# es9023.net
KiCad netlist of a schematic drawn in EAGLE
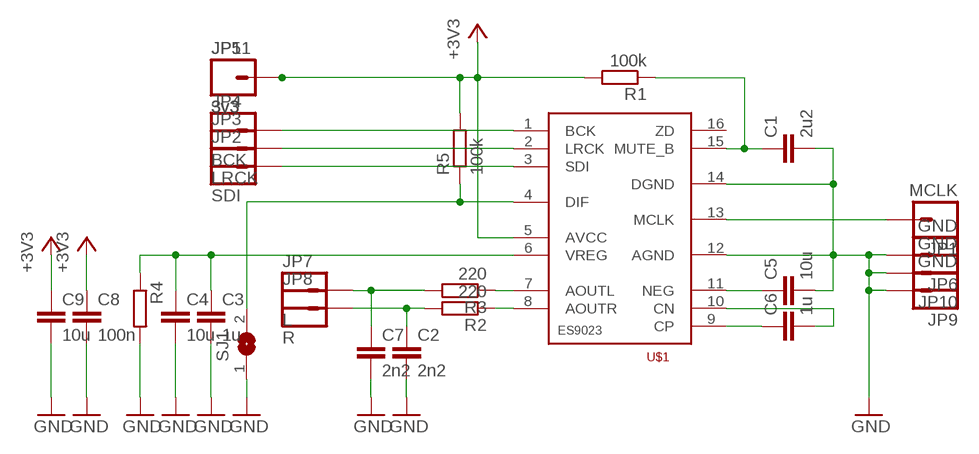
[diagram p0: schematic, sheet 1]

(export (version "E")
  (design (tool "Eeschema 10.0.6"))
  (components
    (comp (ref "C1")
      (value "2u2")
      (footprint "eagle-import:C0805K")
      (libsource (lib "eagle-import") (part "C-EUC0805K"))
    )
    (comp (ref "C2")
      (value "2n2")
      (footprint "eagle-import:C0805K")
      (libsource (lib "eagle-import") (part "C-EUC0805K"))
    )
    (comp (ref "C3")
      (value "1u")
      (footprint "eagle-import:C0805K")
      (libsource (lib "eagle-import") (part "C-EUC0805K"))
    )
    (comp (ref "C4")
      (value "10u")
      (footprint "eagle-import:C0805K")
      (libsource (lib "eagle-import") (part "C-EUC0805K"))
    )
    (comp (ref "C5")
      (value "10u")
      (footprint "eagle-import:C0805K")
      (libsource (lib "eagle-import") (part "C-EUC0805K"))
    )
    (comp (ref "C6")
      (value "1u")
      (footprint "eagle-import:C0805K")
      (libsource (lib "eagle-import") (part "C-EUC0805K"))
    )
    (comp (ref "C7")
      (value "2n2")
      (footprint "eagle-import:C0805K")
      (libsource (lib "eagle-import") (part "C-EUC0805K"))
    )
    (comp (ref "C8")
      (value "100n")
      (footprint "eagle-import:C0805K")
      (libsource (lib "eagle-import") (part "C-EUC0805K"))
    )
    (comp (ref "C9")
      (value "10u")
      (footprint "eagle-import:C0805K")
      (libsource (lib "eagle-import") (part "C-EUC0805K"))
    )
    (comp (ref "JP1")
      (value "MCLK")
      (footprint "eagle-import:1X01_LONGPAD")
      (libsource (lib "eagle-import") (part "M01PTH_LONGPAD"))
    )
    (comp (ref "JP2")
      (value "SDI")
      (footprint "eagle-import:1X01_LONGPAD")
      (libsource (lib "eagle-import") (part "M01PTH_LONGPAD"))
    )
    (comp (ref "JP3")
      (value "LRCK")
      (footprint "eagle-import:1X01_LONGPAD")
      (libsource (lib "eagle-import") (part "M01PTH_LONGPAD"))
    )
    (comp (ref "JP4")
      (value "BCK")
      (footprint "eagle-import:1X01_LONGPAD")
      (libsource (lib "eagle-import") (part "M01PTH_LONGPAD"))
    )
    (comp (ref "JP5")
      (value "3v3")
      (footprint "eagle-import:1X01_LONGPAD")
      (libsource (lib "eagle-import") (part "M01PTH_LONGPAD"))
    )
    (comp (ref "JP6")
      (value "GND")
      (footprint "eagle-import:1X01_LONGPAD")
      (libsource (lib "eagle-import") (part "M01PTH_LONGPAD"))
    )
    (comp (ref "JP7")
      (value "L")
      (footprint "eagle-import:1X01_LONGPAD")
      (libsource (lib "eagle-import") (part "M01PTH_LONGPAD"))
    )
    (comp (ref "JP8")
      (value "R")
      (footprint "eagle-import:1X01_LONGPAD")
      (libsource (lib "eagle-import") (part "M01PTH_LONGPAD"))
    )
    (comp (ref "JP9")
      (value "GND")
      (footprint "eagle-import:1X01_LONGPAD")
      (libsource (lib "eagle-import") (part "M01PTH_LONGPAD"))
    )
    (comp (ref "JP10")
      (value "GND")
      (footprint "eagle-import:1X01_LONGPAD")
      (libsource (lib "eagle-import") (part "M01PTH_LONGPAD"))
    )
    (comp (ref "JP11")
      (value "3v3")
      (footprint "eagle-import:1X01_LONGPAD")
      (libsource (lib "eagle-import") (part "M01PTH_LONGPAD"))
    )
    (comp (ref "R1")
      (value "100k")
      (footprint "eagle-import:M0805")
      (libsource (lib "eagle-import") (part "R-EU_M0805"))
    )
    (comp (ref "R2")
      (value "220")
      (footprint "eagle-import:M0805")
      (libsource (lib "eagle-import") (part "R-EU_M0805"))
    )
    (comp (ref "R3")
      (value "220")
      (footprint "eagle-import:M0805")
      (libsource (lib "eagle-import") (part "R-EU_M0805"))
    )
    (comp (ref "R4")
      (value "R-EU_M0805")
      (footprint "eagle-import:M0805")
      (libsource (lib "eagle-import") (part "R-EU_M0805"))
    )
    (comp (ref "R5")
      (value "100k")
      (footprint "eagle-import:M0805")
      (libsource (lib "eagle-import") (part "R-EU_M0805"))
    )
    (comp (ref "SJ1") (value "SJ") (footprint "eagle-import:SJ") (libsource (lib "eagle-import") (part "SJ")))
    (comp (ref "U$1")
      (value "ES9023-SMD")
      (footprint "eagle-import:SOP16")
      (libsource (lib "eagle-import") (part "ES9023-SMD"))
    )
  )
  (nets
    (net (code "1") (name "+3V3") (class "Default")
      (node (ref "C8") (pin "1") (pinfunction "1_1") (pintype "passive"))
      (node (ref "C9") (pin "1") (pinfunction "1_1") (pintype "passive"))
      (node (ref "JP11") (pin "1") (pinfunction "1_1") (pintype "passive"))
      (node (ref "JP5") (pin "1") (pinfunction "1_1") (pintype "passive"))
      (node (ref "R1") (pin "2") (pinfunction "2_2") (pintype "passive"))
      (node (ref "R5") (pin "2") (pinfunction "2_2") (pintype "passive"))
      (node (ref "U$1") (pin "5") (pinfunction "AVCC_5") (pintype "bidirectional"))
    )
    (net (code "2") (name "GND") (class "Default")
      (node (ref "C1") (pin "2") (pinfunction "2_2") (pintype "passive"))
      (node (ref "C2") (pin "2") (pinfunction "2_2") (pintype "passive"))
      (node (ref "C3") (pin "2") (pinfunction "2_2") (pintype "passive"))
      (node (ref "C4") (pin "2") (pinfunction "2_2") (pintype "passive"))
      (node (ref "C5") (pin "2") (pinfunction "2_2") (pintype "passive"))
      (node (ref "C7") (pin "2") (pinfunction "2_2") (pintype "passive"))
      (node (ref "C8") (pin "2") (pinfunction "2_2") (pintype "passive"))
      (node (ref "C9") (pin "2") (pinfunction "2_2") (pintype "passive"))
      (node (ref "JP10") (pin "1") (pinfunction "1_1") (pintype "passive"))
      (node (ref "JP6") (pin "1") (pinfunction "1_1") (pintype "passive"))
      (node (ref "JP9") (pin "1") (pinfunction "1_1") (pintype "passive"))
      (node (ref "R4") (pin "2") (pinfunction "2_2") (pintype "passive"))
      (node (ref "SJ1") (pin "1") (pinfunction "1_1") (pintype "passive"))
      (node (ref "U$1") (pin "12") (pinfunction "AGND_12") (pintype "bidirectional"))
      (node (ref "U$1") (pin "14") (pinfunction "DGND_14") (pintype "bidirectional"))
    )
    (net (code "3") (name "Net-(C2-Pad1)") (class "Default")
      (node (ref "C2") (pin "1") (pinfunction "1_1") (pintype "passive"))
      (node (ref "JP8") (pin "1") (pinfunction "1_1") (pintype "passive"))
      (node (ref "R2") (pin "2") (pinfunction "2_2") (pintype "passive"))
    )
    (net (code "4") (name "Net-(C7-Pad1)") (class "Default")
      (node (ref "C7") (pin "1") (pinfunction "1_1") (pintype "passive"))
      (node (ref "JP7") (pin "1") (pinfunction "1_1") (pintype "passive"))
      (node (ref "R3") (pin "2") (pinfunction "2_2") (pintype "passive"))
    )
    (net (code "5") (name "Net-(U$1-AOUTL)") (class "Default")
      (node (ref "R3") (pin "1") (pinfunction "1_1") (pintype "passive"))
      (node (ref "U$1") (pin "7") (pinfunction "AOUTL_7") (pintype "bidirectional"))
    )
    (net (code "6") (name "Net-(U$1-AOUTR)") (class "Default")
      (node (ref "R2") (pin "1") (pinfunction "1_1") (pintype "passive"))
      (node (ref "U$1") (pin "8") (pinfunction "AOUTR_8") (pintype "bidirectional"))
    )
    (net (code "7") (name "Net-(U$1-BCK)") (class "Default")
      (node (ref "JP4") (pin "1") (pinfunction "1_1") (pintype "passive"))
      (node (ref "U$1") (pin "1") (pinfunction "BCK_1") (pintype "bidirectional"))
    )
    (net (code "8") (name "Net-(U$1-CN)") (class "Default")
      (node (ref "C6") (pin "2") (pinfunction "2_2") (pintype "passive"))
      (node (ref "U$1") (pin "10") (pinfunction "CN_10") (pintype "bidirectional"))
    )
    (net (code "9") (name "Net-(U$1-CP)") (class "Default")
      (node (ref "C6") (pin "1") (pinfunction "1_1") (pintype "passive"))
      (node (ref "U$1") (pin "9") (pinfunction "CP_9") (pintype "bidirectional"))
    )
    (net (code "10") (name "Net-(U$1-DIF)") (class "Default")
      (node (ref "R5") (pin "1") (pinfunction "1_1") (pintype "passive"))
      (node (ref "SJ1") (pin "2") (pinfunction "2_2") (pintype "passive"))
      (node (ref "U$1") (pin "4") (pinfunction "DIF_4") (pintype "bidirectional"))
    )
    (net (code "11") (name "Net-(U$1-LRCK)") (class "Default")
      (node (ref "JP3") (pin "1") (pinfunction "1_1") (pintype "passive"))
      (node (ref "U$1") (pin "2") (pinfunction "LRCK_2") (pintype "bidirectional"))
    )
    (net (code "12") (name "Net-(U$1-MCLK)") (class "Default")
      (node (ref "JP1") (pin "1") (pinfunction "1_1") (pintype "passive"))
      (node (ref "U$1") (pin "13") (pinfunction "MCLK_13") (pintype "bidirectional"))
    )
    (net (code "13") (name "Net-(U$1-MUTE_B)") (class "Default")
      (node (ref "C1") (pin "1") (pinfunction "1_1") (pintype "passive"))
      (node (ref "R1") (pin "1") (pinfunction "1_1") (pintype "passive"))
      (node (ref "U$1") (pin "15") (pinfunction "MUTE_B_15") (pintype "bidirectional"))
    )
    (net (code "14") (name "Net-(U$1-NEG)") (class "Default")
      (node (ref "C5") (pin "1") (pinfunction "1_1") (pintype "passive"))
      (node (ref "U$1") (pin "11") (pinfunction "NEG_11") (pintype "bidirectional"))
    )
    (net (code "15") (name "Net-(U$1-SDI)") (class "Default")
      (node (ref "JP2") (pin "1") (pinfunction "1_1") (pintype "passive"))
      (node (ref "U$1") (pin "3") (pinfunction "SDI_3") (pintype "bidirectional"))
    )
    (net (code "16") (name "Net-(U$1-VREG)") (class "Default")
      (node (ref "C3") (pin "1") (pinfunction "1_1") (pintype "passive"))
      (node (ref "C4") (pin "1") (pinfunction "1_1") (pintype "passive"))
      (node (ref "R4") (pin "1") (pinfunction "1_1") (pintype "passive"))
      (node (ref "U$1") (pin "6") (pinfunction "VREG_6") (pintype "bidirectional"))
    )
    (net (code "17") (name "unconnected-(U$1-ZD-Pad16)") (class "Default")
      (node (ref "U$1") (pin "16") (pinfunction "ZD_16") (pintype "bidirectional"))
    )
  )
)
